# CON_MCU.net
KiCad netlist of a schematic drawn in Altium Designer
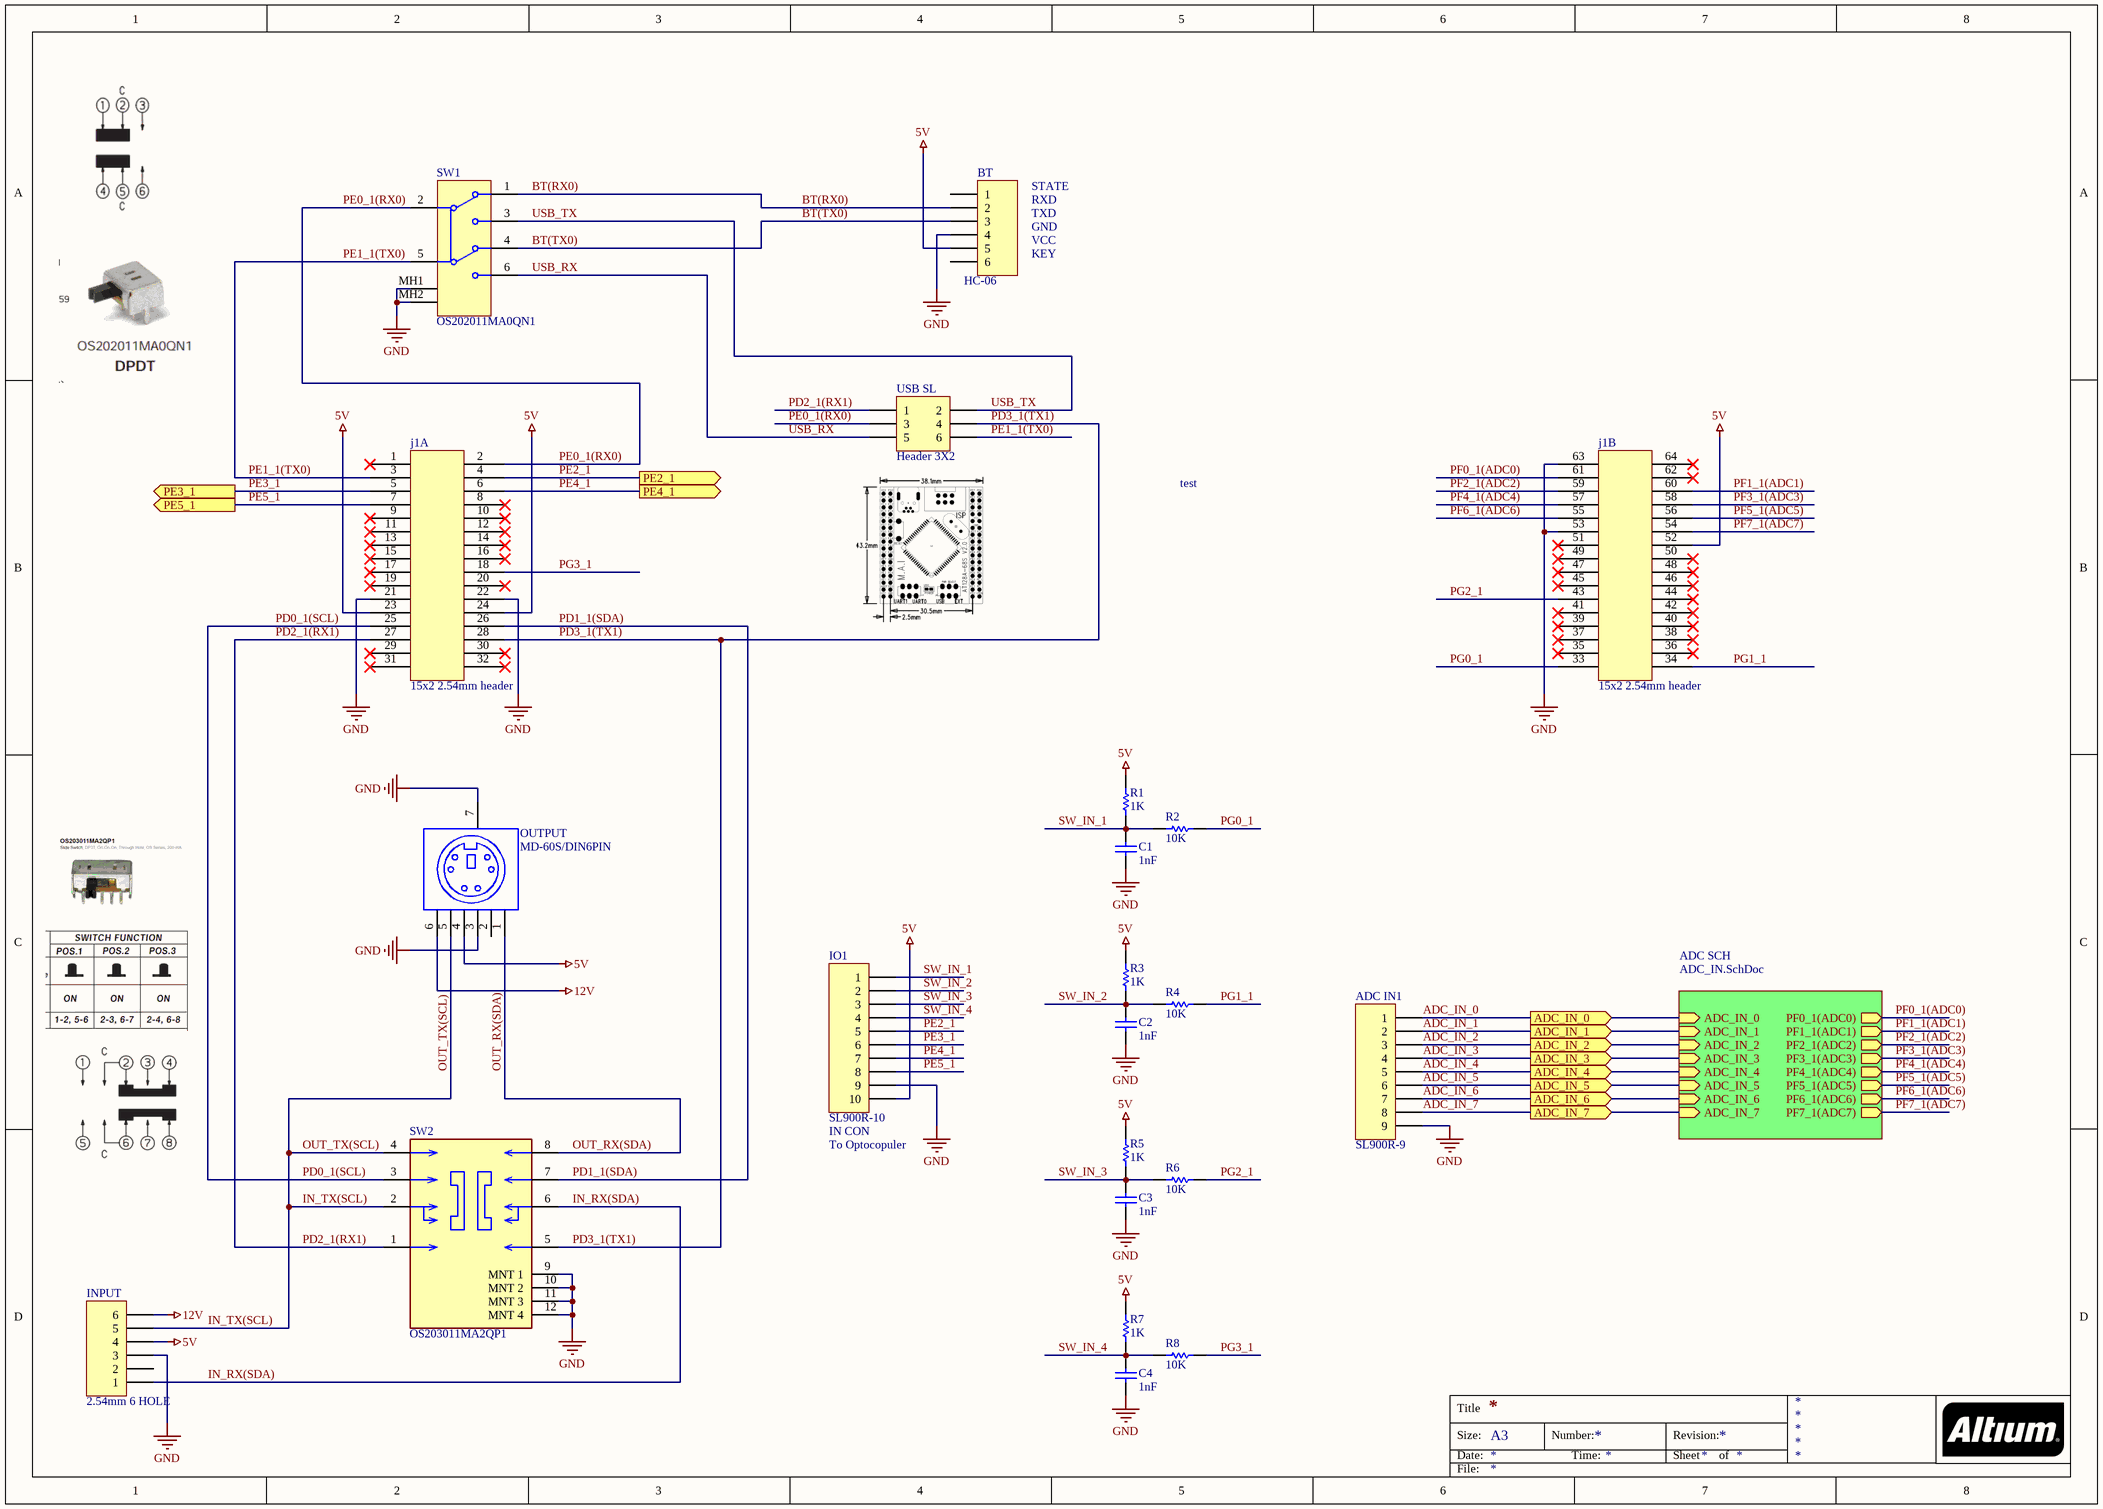
[diagram p0: CON_MCU.SchDoc]

(export (version "E")
  (design (tool "Eeschema 10.0.6"))
  (components
    (comp (ref "ADC IN1")
      (value "SL900R-9")
      (footprint "SR-900R-9")
      (description "Header, 9-Pin")
      (fields (field (name "PUBLISHER") "Altium Limited"))
      (libsource (lib "project") (part "Header 9"))
    )
    (comp (ref "BT")
      (value "HC-06")
      (footprint "HC-06")
      (description "Header, 6-Pin")
      (fields (field (name "PUBLISHER") "Altium Limited"))
      (libsource (lib "") (part "Header 6_1"))
    )
    (comp (ref "C1")
      (value "1nF")
      (footprint "CAPC2013X140X50NL20T25")
      (fields
        (field (name "MANUFACTURER") "AVX Interconnect / Elco")
        (field (name "PART NUMBER") "08051A102JAT2A")
      )
      (libsource (lib "project") (part "CAP"))
    )
    (comp (ref "C2")
      (value "1nF")
      (footprint "CAPC2013X140X50NL20T25")
      (fields
        (field (name "MANUFACTURER") "AVX Interconnect / Elco")
        (field (name "PART NUMBER") "08051A102JAT2A")
      )
      (libsource (lib "project") (part "CAP"))
    )
    (comp (ref "C3")
      (value "1nF")
      (footprint "CAPC2013X140X50NL20T25")
      (fields
        (field (name "MANUFACTURER") "AVX Interconnect / Elco")
        (field (name "PART NUMBER") "08051A102JAT2A")
      )
      (libsource (lib "project") (part "CAP"))
    )
    (comp (ref "C4")
      (value "1nF")
      (footprint "CAPC2013X140X50NL20T25")
      (fields
        (field (name "MANUFACTURER") "AVX Interconnect / Elco")
        (field (name "PART NUMBER") "08051A102JAT2A")
      )
      (libsource (lib "project") (part "CAP"))
    )
    (comp (ref "INPUT")
      (value "2.54mm 6 HOLE")
      (footprint "SMW200-06")
      (description "Header, 6-Pin")
      (fields (field (name "PUBLISHER") "Altium Limited"))
      (libsource (lib "project") (part "Header 6"))
    )
    (comp (ref "IO1")
      (value "SL900R-10")
      (footprint "SR-900R-10")
      (description "Header, 10-Pin")
      (fields (field (name "PUBLISHER") "Altium Limited"))
      (libsource (lib "project") (part "Header 10"))
    )
    (comp (ref "j1")
      (value "15x2 2.54mm header")
      (footprint "Component_1")
      (libsource (lib "") (part "Component_1_1"))
    )
    (comp (ref "OUTPUT")
      (value "MD-60S/DIN6PIN")
      (footprint "CUI-MD-60S_V")
      (description "Right Angle Mini DIN Connector, 100 Vac, 12 Vdc, -40 to 85 degC, 6-Pin THD, RoHS, Bulk")
      (fields (field (name "MANUFACTURER") "CUI Inc"))
      (libsource (lib "project") (part "CUI-MD-60S-6"))
    )
    (comp (ref "R1")
      (value "1K")
      (footprint "RESC2113X50X35ML15T15")
      (description "Chip Resistor, 4.7 KOhm, +/- 1%, 0.125 W, -55 to 155 degC, 0805 (2012 Metric), RoHS, Tape and Reel")
      (fields (field (name "TOLERANCE") "1%") (field (name "MANUFACTURER") "Vishay Semiconductor"))
      (libsource (lib "project") (part "RES-2"))
    )
    (comp (ref "R2")
      (value "10K")
      (footprint "RESC2113X50X35ML15T15")
      (description "Chip Resistor, 4.7 KOhm, +/- 1%, 0.125 W, -55 to 155 degC, 0805 (2012 Metric), RoHS, Tape and Reel")
      (fields (field (name "TOLERANCE") "1%") (field (name "MANUFACTURER") "Vishay Semiconductor"))
      (libsource (lib "project") (part "RES-2"))
    )
    (comp (ref "R3")
      (value "1K")
      (footprint "RESC2113X50X35ML15T15")
      (description "Chip Resistor, 4.7 KOhm, +/- 1%, 0.125 W, -55 to 155 degC, 0805 (2012 Metric), RoHS, Tape and Reel")
      (fields (field (name "TOLERANCE") "1%") (field (name "MANUFACTURER") "Vishay Semiconductor"))
      (libsource (lib "project") (part "RES-2"))
    )
    (comp (ref "R4")
      (value "10K")
      (footprint "RESC2113X50X35ML15T15")
      (description "Chip Resistor, 4.7 KOhm, +/- 1%, 0.125 W, -55 to 155 degC, 0805 (2012 Metric), RoHS, Tape and Reel")
      (fields (field (name "TOLERANCE") "1%") (field (name "MANUFACTURER") "Vishay Semiconductor"))
      (libsource (lib "project") (part "RES-2"))
    )
    (comp (ref "R5")
      (value "1K")
      (footprint "RESC2113X50X35ML15T15")
      (description "Chip Resistor, 4.7 KOhm, +/- 1%, 0.125 W, -55 to 155 degC, 0805 (2012 Metric), RoHS, Tape and Reel")
      (fields (field (name "TOLERANCE") "1%") (field (name "MANUFACTURER") "Vishay Semiconductor"))
      (libsource (lib "project") (part "RES-2"))
    )
    (comp (ref "R6")
      (value "10K")
      (footprint "RESC2113X50X35ML15T15")
      (description "Chip Resistor, 4.7 KOhm, +/- 1%, 0.125 W, -55 to 155 degC, 0805 (2012 Metric), RoHS, Tape and Reel")
      (fields (field (name "TOLERANCE") "1%") (field (name "MANUFACTURER") "Vishay Semiconductor"))
      (libsource (lib "project") (part "RES-2"))
    )
    (comp (ref "R7")
      (value "1K")
      (footprint "RESC2113X50X35ML15T15")
      (description "Chip Resistor, 4.7 KOhm, +/- 1%, 0.125 W, -55 to 155 degC, 0805 (2012 Metric), RoHS, Tape and Reel")
      (fields (field (name "TOLERANCE") "1%") (field (name "MANUFACTURER") "Vishay Semiconductor"))
      (libsource (lib "project") (part "RES-2"))
    )
    (comp (ref "R8")
      (value "10K")
      (footprint "RESC2113X50X35ML15T15")
      (description "Chip Resistor, 4.7 KOhm, +/- 1%, 0.125 W, -55 to 155 degC, 0805 (2012 Metric), RoHS, Tape and Reel")
      (fields (field (name "TOLERANCE") "1%") (field (name "MANUFACTURER") "Vishay Semiconductor"))
      (libsource (lib "project") (part "RES-2"))
    )
    (comp (ref "SW1")
      (value "OS202011MA0QN1")
      (footprint "TE-1825289-1_V")
      (description "Slide Switch, MHS Series, Double Pole, Vertical, 125 V (AC), -20 to 85 degC, 6-Pin THD, RoHS, Bulk")
      (libsource (lib "project") (part "SW-DPDT-6"))
    )
    (comp (ref "SW2")
      (value "OS203011MA2QP1")
      (footprint "FP-EG2301-MFG")
      (description "SWITCH SLIDE DP3T 200MA 30V")
      (fields (field (name "MANUFACTURER PART NUMBER") "EG2301") (field (name "MANUFACTURER") "E-Switch"))
      (libsource (lib "project") (part "CMP-17877-000002-1"))
    )
    (comp (ref "USB SL")
      (value "Header 3X2")
      (footprint "USB SEL")
      (description "Header, 3-Pin, Dual row")
      (fields (field (name "PUBLISHER") "Altium Limited"))
      (libsource (lib "project") (part "Header 3X2"))
    )
  )
  (nets
    (net (code "1") (name "/ADC_IN_0") (class "Default")
      (node (ref "ADC IN1") (pin "1") (pinfunction "1_1") (pintype "passive"))
    )
    (net (code "2") (name "/ADC_IN_1") (class "Default")
      (node (ref "ADC IN1") (pin "2") (pinfunction "2_2") (pintype "passive"))
    )
    (net (code "3") (name "/ADC_IN_2") (class "Default")
      (node (ref "ADC IN1") (pin "3") (pinfunction "3_3") (pintype "passive"))
    )
    (net (code "4") (name "/ADC_IN_3") (class "Default")
      (node (ref "ADC IN1") (pin "4") (pinfunction "4_4") (pintype "passive"))
    )
    (net (code "5") (name "/ADC_IN_4") (class "Default")
      (node (ref "ADC IN1") (pin "5") (pinfunction "5_5") (pintype "passive"))
    )
    (net (code "6") (name "/ADC_IN_5") (class "Default")
      (node (ref "ADC IN1") (pin "6") (pinfunction "6_6") (pintype "passive"))
    )
    (net (code "7") (name "/ADC_IN_6") (class "Default")
      (node (ref "ADC IN1") (pin "7") (pinfunction "7_7") (pintype "passive"))
    )
    (net (code "8") (name "/ADC_IN_7") (class "Default")
      (node (ref "ADC IN1") (pin "8") (pinfunction "8_8") (pintype "passive"))
    )
    (net (code "9") (name "/BT(RX0)") (class "Default")
      (node (ref "BT") (pin "2") (pinfunction "2_2") (pintype "passive"))
      (node (ref "SW1") (pin "1") (pinfunction "1_1") (pintype "passive"))
    )
    (net (code "10") (name "/BT(TX0)") (class "Default")
      (node (ref "BT") (pin "3") (pinfunction "3_3") (pintype "passive"))
      (node (ref "SW1") (pin "4") (pinfunction "4_4") (pintype "passive"))
    )
    (net (code "11") (name "/IN_RX(SDA)") (class "Default")
      (node (ref "INPUT") (pin "1") (pinfunction "1_1") (pintype "passive"))
      (node (ref "SW2") (pin "6") (pinfunction "6_6") (pintype "passive"))
    )
    (net (code "12") (name "/IN_TX(SCL)") (class "Default")
      (node (ref "INPUT") (pin "5") (pinfunction "5_5") (pintype "passive"))
      (node (ref "OUTPUT") (pin "5") (pinfunction "5_5") (pintype "passive"))
      (node (ref "SW2") (pin "2") (pinfunction "2_2") (pintype "passive"))
      (node (ref "SW2") (pin "4") (pinfunction "4_4") (pintype "passive"))
    )
    (net (code "13") (name "/OUT_RX(SDA)") (class "Default")
      (node (ref "OUTPUT") (pin "1") (pinfunction "1_1") (pintype "passive"))
      (node (ref "SW2") (pin "8") (pinfunction "8_8") (pintype "passive"))
    )
    (net (code "14") (name "/PD0_1(SCL)") (class "Default")
      (node (ref "SW2") (pin "3") (pinfunction "3_3") (pintype "passive"))
      (node (ref "j1") (pin "25") (pintype "passive"))
    )
    (net (code "15") (name "/PD1_1(SDA)") (class "Default")
      (node (ref "SW2") (pin "7") (pinfunction "7_7") (pintype "passive"))
      (node (ref "j1") (pin "26") (pintype "passive"))
    )
    (net (code "16") (name "/PD2_1(RX1)") (class "Default")
      (node (ref "SW2") (pin "1") (pinfunction "1_1") (pintype "passive"))
      (node (ref "USB SL") (pin "1") (pinfunction "1_1") (pintype "passive"))
      (node (ref "j1") (pin "27") (pintype "passive"))
    )
    (net (code "17") (name "/PD3_1(TX1)") (class "Default")
      (node (ref "SW2") (pin "5") (pinfunction "5_5") (pintype "passive"))
      (node (ref "USB SL") (pin "4") (pinfunction "4_4") (pintype "passive"))
      (node (ref "j1") (pin "28") (pintype "passive"))
    )
    (net (code "18") (name "/PE0_1(RX0)") (class "Default")
      (node (ref "SW1") (pin "2") (pinfunction "2_2") (pintype "passive"))
      (node (ref "USB SL") (pin "3") (pinfunction "3_3") (pintype "passive"))
      (node (ref "j1") (pin "2") (pintype "passive"))
    )
    (net (code "19") (name "/PE1_1(TX0)") (class "Default")
      (node (ref "SW1") (pin "5") (pinfunction "5_5") (pintype "passive"))
      (node (ref "USB SL") (pin "6") (pinfunction "6_6") (pintype "passive"))
      (node (ref "j1") (pin "3") (pintype "passive"))
    )
    (net (code "20") (name "/PE2_1") (class "Default")
      (node (ref "IO1") (pin "5") (pinfunction "5_5") (pintype "passive"))
      (node (ref "j1") (pin "4") (pintype "passive"))
    )
    (net (code "21") (name "/PE3_1") (class "Default")
      (node (ref "IO1") (pin "6") (pinfunction "6_6") (pintype "passive"))
      (node (ref "j1") (pin "5") (pintype "passive"))
    )
    (net (code "22") (name "/PE4_1") (class "Default")
      (node (ref "IO1") (pin "7") (pinfunction "7_7") (pintype "passive"))
      (node (ref "j1") (pin "6") (pintype "passive"))
    )
    (net (code "23") (name "/PE5_1") (class "Default")
      (node (ref "IO1") (pin "8") (pinfunction "8_8") (pintype "passive"))
      (node (ref "j1") (pin "7") (pintype "passive"))
    )
    (net (code "24") (name "/PF0_1(ADC0)") (class "Default") (node (ref "j1") (pin "61") (pintype "passive")))
    (net (code "25") (name "/PF1_1(ADC1)") (class "Default") (node (ref "j1") (pin "60") (pintype "passive")))
    (net (code "26") (name "/PF2_1(ADC2)") (class "Default") (node (ref "j1") (pin "59") (pintype "passive")))
    (net (code "27") (name "/PF3_1(ADC3)") (class "Default") (node (ref "j1") (pin "58") (pintype "passive")))
    (net (code "28") (name "/PF4_1(ADC4)") (class "Default") (node (ref "j1") (pin "57") (pintype "passive")))
    (net (code "29") (name "/PF5_1(ADC5)") (class "Default") (node (ref "j1") (pin "56") (pintype "passive")))
    (net (code "30") (name "/PF6_1(ADC6)") (class "Default") (node (ref "j1") (pin "55") (pintype "passive")))
    (net (code "31") (name "/PF7_1(ADC7)") (class "Default") (node (ref "j1") (pin "54") (pintype "passive")))
    (net (code "32") (name "/PG0_1") (class "Default")
      (node (ref "R2") (pin "1") (pinfunction "1_1") (pintype "passive"))
      (node (ref "j1") (pin "33") (pintype "passive"))
    )
    (net (code "33") (name "/PG1_1") (class "Default")
      (node (ref "R4") (pin "1") (pinfunction "1_1") (pintype "passive"))
      (node (ref "j1") (pin "34") (pintype "passive"))
    )
    (net (code "34") (name "/PG2_1") (class "Default")
      (node (ref "R6") (pin "1") (pinfunction "1_1") (pintype "passive"))
      (node (ref "j1") (pin "43") (pintype "passive"))
    )
    (net (code "35") (name "/PG3_1") (class "Default")
      (node (ref "R8") (pin "1") (pinfunction "1_1") (pintype "passive"))
      (node (ref "j1") (pin "18") (pintype "passive"))
    )
    (net (code "36") (name "/SW_IN_1") (class "Default")
      (node (ref "C1") (pin "2") (pinfunction "2_2") (pintype "passive"))
      (node (ref "IO1") (pin "1") (pinfunction "1_1") (pintype "passive"))
      (node (ref "R1") (pin "1") (pinfunction "1_1") (pintype "passive"))
      (node (ref "R2") (pin "2") (pinfunction "2_2") (pintype "passive"))
    )
    (net (code "37") (name "/SW_IN_2") (class "Default")
      (node (ref "C2") (pin "2") (pinfunction "2_2") (pintype "passive"))
      (node (ref "IO1") (pin "2") (pinfunction "2_2") (pintype "passive"))
      (node (ref "R3") (pin "1") (pinfunction "1_1") (pintype "passive"))
      (node (ref "R4") (pin "2") (pinfunction "2_2") (pintype "passive"))
    )
    (net (code "38") (name "/SW_IN_3") (class "Default")
      (node (ref "C3") (pin "2") (pinfunction "2_2") (pintype "passive"))
      (node (ref "IO1") (pin "3") (pinfunction "3_3") (pintype "passive"))
      (node (ref "R5") (pin "1") (pinfunction "1_1") (pintype "passive"))
      (node (ref "R6") (pin "2") (pinfunction "2_2") (pintype "passive"))
    )
    (net (code "39") (name "/SW_IN_4") (class "Default")
      (node (ref "C4") (pin "2") (pinfunction "2_2") (pintype "passive"))
      (node (ref "IO1") (pin "4") (pinfunction "4_4") (pintype "passive"))
      (node (ref "R7") (pin "1") (pinfunction "1_1") (pintype "passive"))
      (node (ref "R8") (pin "2") (pinfunction "2_2") (pintype "passive"))
    )
    (net (code "40") (name "/USB_RX") (class "Default")
      (node (ref "SW1") (pin "6") (pinfunction "6_6") (pintype "passive"))
      (node (ref "USB SL") (pin "5") (pinfunction "5_5") (pintype "passive"))
    )
    (net (code "41") (name "/USB_TX") (class "Default")
      (node (ref "SW1") (pin "3") (pinfunction "3_3") (pintype "passive"))
      (node (ref "USB SL") (pin "2") (pinfunction "2_2") (pintype "passive"))
    )
    (net (code "42") (name "5V") (class "Default")
      (node (ref "BT") (pin "5") (pinfunction "5_5") (pintype "passive"))
      (node (ref "INPUT") (pin "4") (pinfunction "4_4") (pintype "passive"))
      (node (ref "IO1") (pin "10") (pinfunction "10_10") (pintype "passive"))
      (node (ref "OUTPUT") (pin "4") (pinfunction "4_4") (pintype "passive"))
      (node (ref "R1") (pin "2") (pinfunction "2_2") (pintype "passive"))
      (node (ref "R3") (pin "2") (pinfunction "2_2") (pintype "passive"))
      (node (ref "R5") (pin "2") (pinfunction "2_2") (pintype "passive"))
      (node (ref "R7") (pin "2") (pinfunction "2_2") (pintype "passive"))
      (node (ref "j1") (pin "23") (pintype "passive"))
      (node (ref "j1") (pin "24") (pintype "passive"))
      (node (ref "j1") (pin "52") (pintype "passive"))
    )
    (net (code "43") (name "12V") (class "Default")
      (node (ref "INPUT") (pin "6") (pinfunction "6_6") (pintype "passive"))
      (node (ref "OUTPUT") (pin "6") (pinfunction "6_6") (pintype "passive"))
    )
    (net (code "44") (name "GND") (class "Default")
      (node (ref "ADC IN1") (pin "9") (pinfunction "9_9") (pintype "passive"))
      (node (ref "BT") (pin "4") (pinfunction "4_4") (pintype "passive"))
      (node (ref "C1") (pin "1") (pinfunction "1_1") (pintype "passive"))
      (node (ref "C2") (pin "1") (pinfunction "1_1") (pintype "passive"))
      (node (ref "C3") (pin "1") (pinfunction "1_1") (pintype "passive"))
      (node (ref "C4") (pin "1") (pinfunction "1_1") (pintype "passive"))
      (node (ref "INPUT") (pin "3") (pinfunction "3_3") (pintype "passive"))
      (node (ref "IO1") (pin "9") (pinfunction "9_9") (pintype "passive"))
      (node (ref "OUTPUT") (pin "3") (pinfunction "3_3") (pintype "passive"))
      (node (ref "OUTPUT") (pin "7") (pinfunction "7_7") (pintype "passive"))
      (node (ref "SW1") (pin "MH1") (pinfunction "MH1_MH1") (pintype "passive"))
      (node (ref "SW1") (pin "MH2") (pinfunction "MH2_MH2") (pintype "passive"))
      (node (ref "SW2") (pin "10") (pinfunction "MNT_2_10") (pintype "passive"))
      (node (ref "SW2") (pin "11") (pinfunction "MNT_3_11") (pintype "passive"))
      (node (ref "SW2") (pin "12") (pinfunction "MNT_4_12") (pintype "passive"))
      (node (ref "SW2") (pin "9") (pinfunction "MNT_1_9") (pintype "passive"))
      (node (ref "j1") (pin "21") (pintype "passive"))
      (node (ref "j1") (pin "22") (pintype "passive"))
      (node (ref "j1") (pin "53") (pintype "passive"))
      (node (ref "j1") (pin "63") (pintype "passive"))
    )
    (net (code "45") (name "unconnected-(BT-Pad1)") (class "Default")
      (node (ref "BT") (pin "1") (pinfunction "1_1") (pintype "passive"))
    )
    (net (code "46") (name "unconnected-(BT-Pad6)") (class "Default")
      (node (ref "BT") (pin "6") (pinfunction "6_6") (pintype "passive"))
    )
    (net (code "47") (name "unconnected-(INPUT-Pad2)") (class "Default")
      (node (ref "INPUT") (pin "2") (pinfunction "2_2") (pintype "passive"))
    )
    (net (code "48") (name "unconnected-(OUTPUT-Pad2)") (class "Default")
      (node (ref "OUTPUT") (pin "2") (pinfunction "2_2") (pintype "passive"))
    )
    (net (code "49") (name "unconnected-(j1-Pad1)") (class "Default")
      (node (ref "j1") (pin "1") (pintype "passive+no_connect"))
    )
    (net (code "50") (name "unconnected-(j1-Pad8)") (class "Default")
      (node (ref "j1") (pin "8") (pintype "passive+no_connect"))
    )
    (net (code "51") (name "unconnected-(j1-Pad9)") (class "Default")
      (node (ref "j1") (pin "9") (pintype "passive+no_connect"))
    )
    (net (code "52") (name "unconnected-(j1-Pad10)") (class "Default")
      (node (ref "j1") (pin "10") (pintype "passive+no_connect"))
    )
    (net (code "53") (name "unconnected-(j1-Pad11)") (class "Default")
      (node (ref "j1") (pin "11") (pintype "passive+no_connect"))
    )
    (net (code "54") (name "unconnected-(j1-Pad12)") (class "Default")
      (node (ref "j1") (pin "12") (pintype "passive+no_connect"))
    )
    (net (code "55") (name "unconnected-(j1-Pad13)") (class "Default")
      (node (ref "j1") (pin "13") (pintype "passive+no_connect"))
    )
    (net (code "56") (name "unconnected-(j1-Pad14)") (class "Default")
      (node (ref "j1") (pin "14") (pintype "passive+no_connect"))
    )
    (net (code "57") (name "unconnected-(j1-Pad15)") (class "Default")
      (node (ref "j1") (pin "15") (pintype "passive+no_connect"))
    )
    (net (code "58") (name "unconnected-(j1-Pad16)") (class "Default")
      (node (ref "j1") (pin "16") (pintype "passive+no_connect"))
    )
    (net (code "59") (name "unconnected-(j1-Pad17)") (class "Default")
      (node (ref "j1") (pin "17") (pintype "passive+no_connect"))
    )
    (net (code "60") (name "unconnected-(j1-Pad19)") (class "Default")
      (node (ref "j1") (pin "19") (pintype "passive+no_connect"))
    )
    (net (code "61") (name "unconnected-(j1-Pad20)") (class "Default")
      (node (ref "j1") (pin "20") (pintype "passive+no_connect"))
    )
    (net (code "62") (name "unconnected-(j1-Pad29)") (class "Default")
      (node (ref "j1") (pin "29") (pintype "passive+no_connect"))
    )
    (net (code "63") (name "unconnected-(j1-Pad30)") (class "Default")
      (node (ref "j1") (pin "30") (pintype "passive+no_connect"))
    )
    (net (code "64") (name "unconnected-(j1-Pad31)") (class "Default")
      (node (ref "j1") (pin "31") (pintype "passive+no_connect"))
    )
    (net (code "65") (name "unconnected-(j1-Pad32)") (class "Default")
      (node (ref "j1") (pin "32") (pintype "passive+no_connect"))
    )
    (net (code "66") (name "unconnected-(j1-Pad35)") (class "Default")
      (node (ref "j1") (pin "35") (pintype "passive+no_connect"))
    )
    (net (code "67") (name "unconnected-(j1-Pad36)") (class "Default")
      (node (ref "j1") (pin "36") (pintype "passive+no_connect"))
    )
    (net (code "68") (name "unconnected-(j1-Pad37)") (class "Default")
      (node (ref "j1") (pin "37") (pintype "passive+no_connect"))
    )
    (net (code "69") (name "unconnected-(j1-Pad38)") (class "Default")
      (node (ref "j1") (pin "38") (pintype "passive+no_connect"))
    )
    (net (code "70") (name "unconnected-(j1-Pad39)") (class "Default")
      (node (ref "j1") (pin "39") (pintype "passive+no_connect"))
    )
    (net (code "71") (name "unconnected-(j1-Pad40)") (class "Default")
      (node (ref "j1") (pin "40") (pintype "passive+no_connect"))
    )
    (net (code "72") (name "unconnected-(j1-Pad41)") (class "Default")
      (node (ref "j1") (pin "41") (pintype "passive+no_connect"))
    )
    (net (code "73") (name "unconnected-(j1-Pad42)") (class "Default")
      (node (ref "j1") (pin "42") (pintype "passive+no_connect"))
    )
    (net (code "74") (name "unconnected-(j1-Pad44)") (class "Default")
      (node (ref "j1") (pin "44") (pintype "passive+no_connect"))
    )
    (net (code "75") (name "unconnected-(j1-Pad45)") (class "Default")
      (node (ref "j1") (pin "45") (pintype "passive+no_connect"))
    )
    (net (code "76") (name "unconnected-(j1-Pad46)") (class "Default")
      (node (ref "j1") (pin "46") (pintype "passive+no_connect"))
    )
    (net (code "77") (name "unconnected-(j1-Pad47)") (class "Default")
      (node (ref "j1") (pin "47") (pintype "passive+no_connect"))
    )
    (net (code "78") (name "unconnected-(j1-Pad48)") (class "Default")
      (node (ref "j1") (pin "48") (pintype "passive+no_connect"))
    )
    (net (code "79") (name "unconnected-(j1-Pad49)") (class "Default")
      (node (ref "j1") (pin "49") (pintype "passive+no_connect"))
    )
    (net (code "80") (name "unconnected-(j1-Pad50)") (class "Default")
      (node (ref "j1") (pin "50") (pintype "passive+no_connect"))
    )
    (net (code "81") (name "unconnected-(j1-Pad51)") (class "Default")
      (node (ref "j1") (pin "51") (pintype "passive+no_connect"))
    )
    (net (code "82") (name "unconnected-(j1-Pad62)") (class "Default")
      (node (ref "j1") (pin "62") (pintype "passive+no_connect"))
    )
    (net (code "83") (name "unconnected-(j1-Pad64)") (class "Default")
      (node (ref "j1") (pin "64") (pintype "passive+no_connect"))
    )
  )
)
